# ESC3_1.net
KiCad netlist of a schematic drawn in Altium Designer
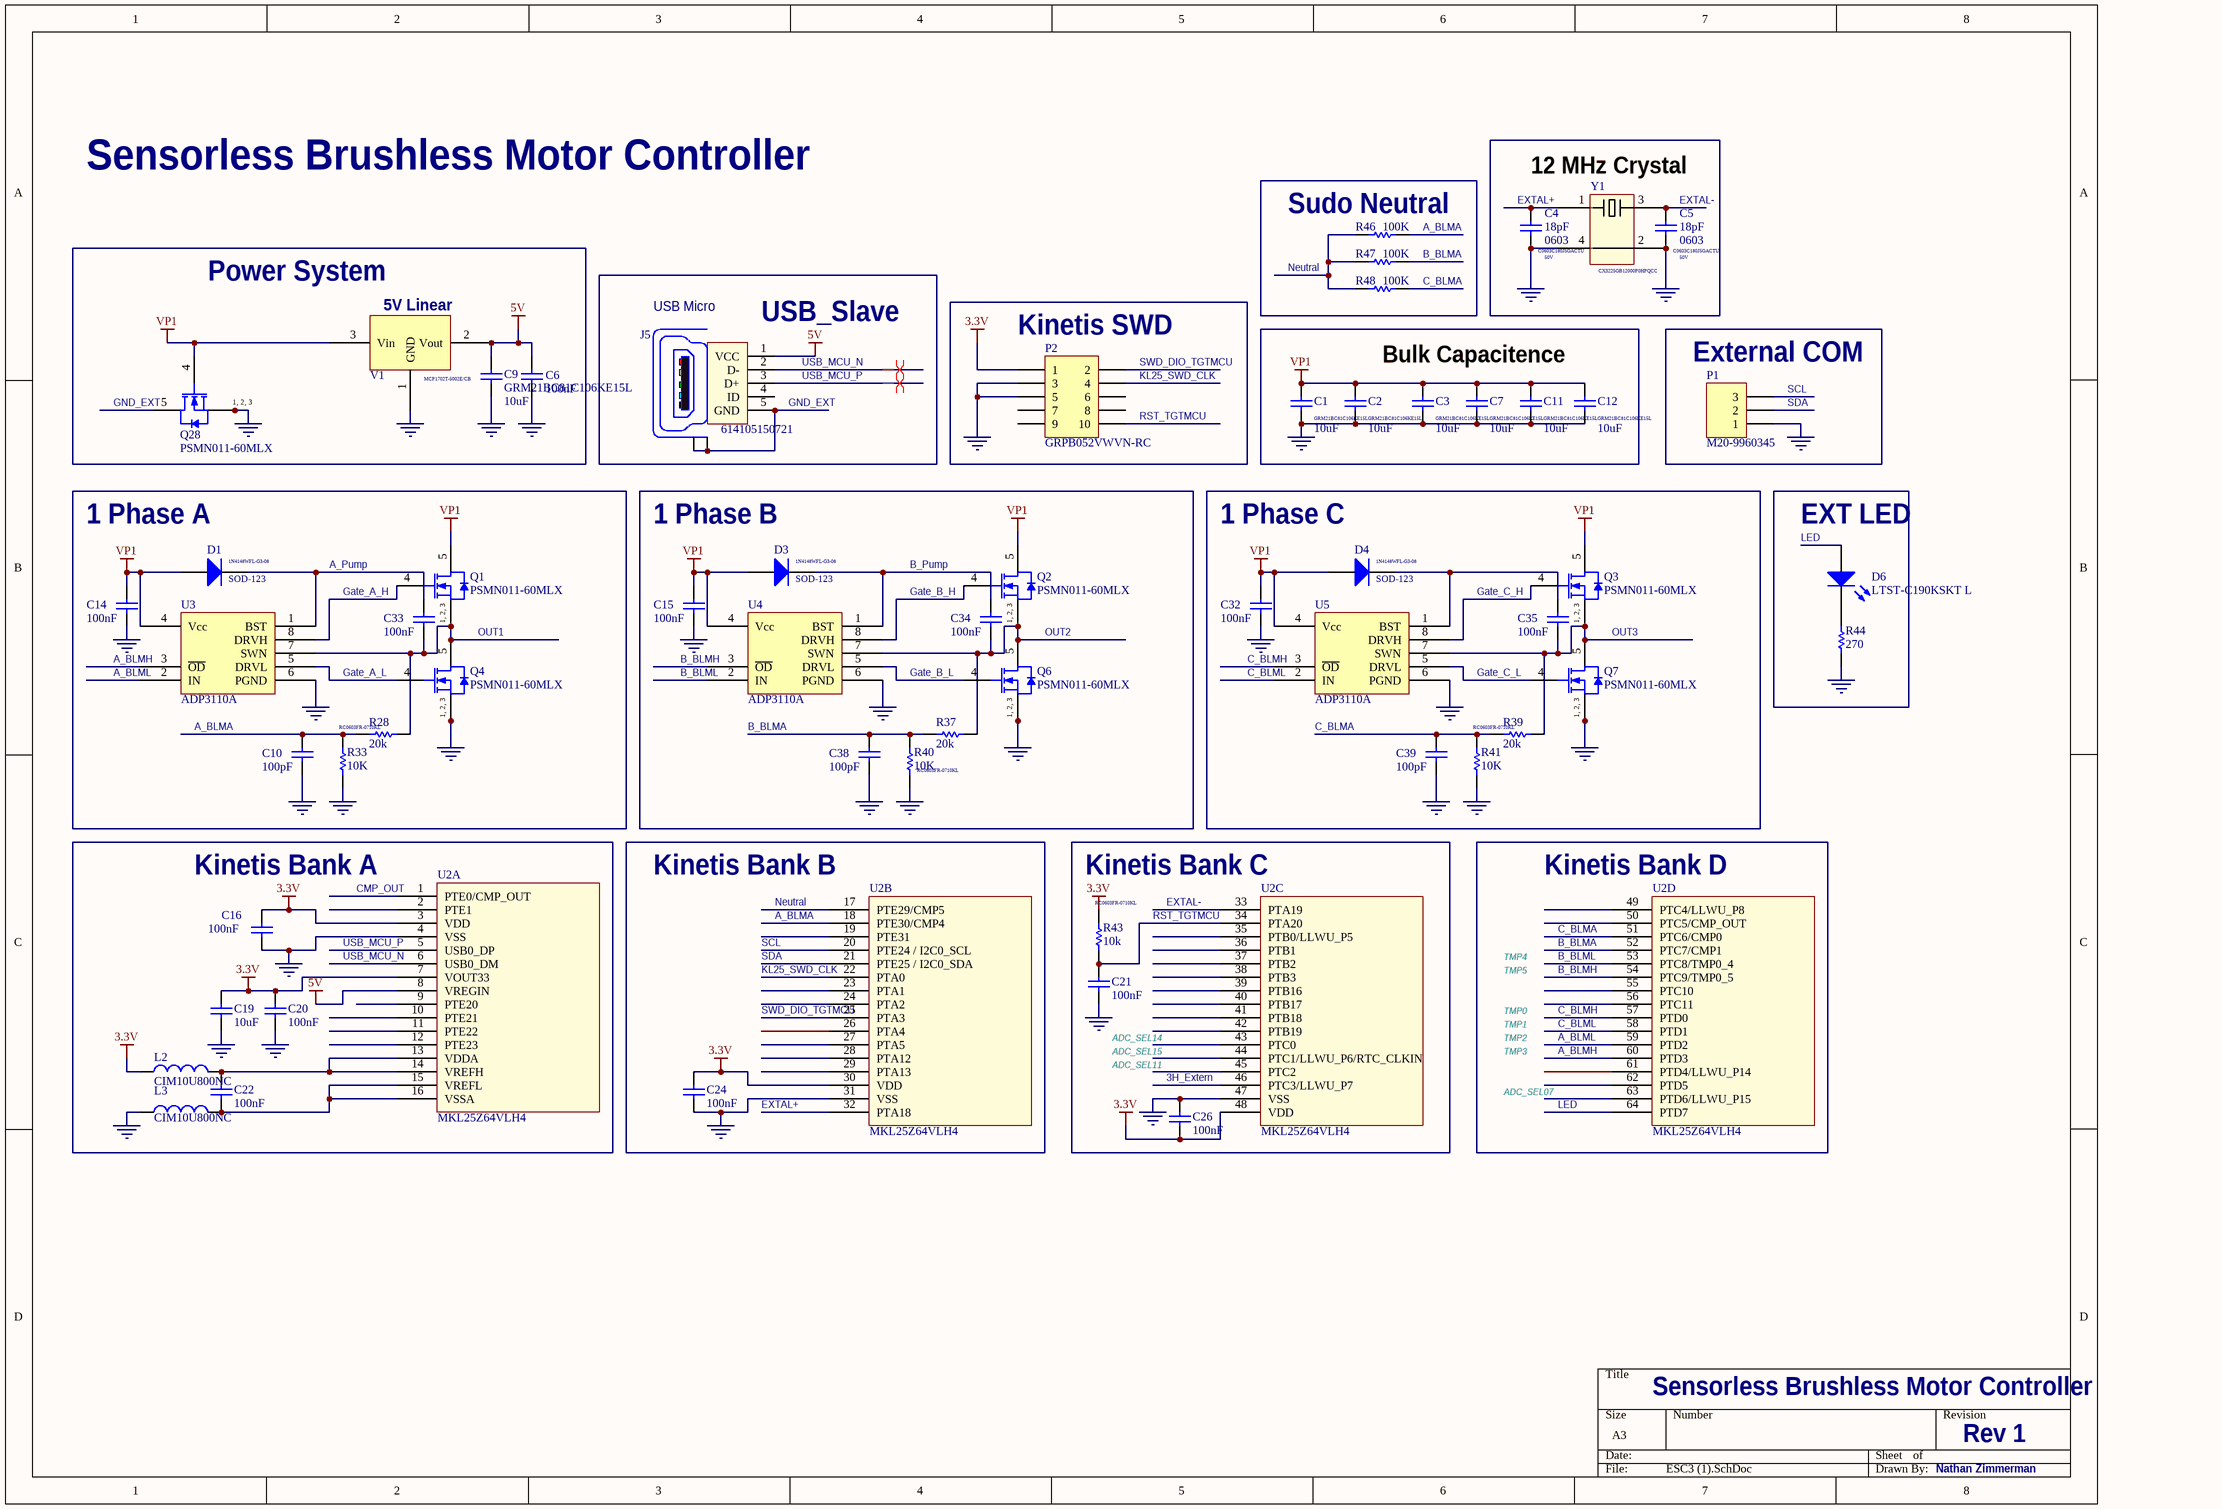
[diagram p0: ESC3 (1).SchDoc]

(export (version "E")
  (design (tool "Eeschema 10.0.6"))
  (components
    (comp (ref "C1")
      (value "GRM21BC81C106KE15L")
      (footprint "6-0805_MC")
      (fields (field (name "ALTIUM_VALUE") "10uF") (field (name "PUBLISHER") "Altium Limited"))
      (libsource (lib "Miscellaneous Devices") (part "Cap"))
    )
    (comp (ref "C2")
      (value "GRM21BC81C106KE15L")
      (footprint "6-0805_MC")
      (fields (field (name "ALTIUM_VALUE") "10uF") (field (name "PUBLISHER") "Altium Limited"))
      (libsource (lib "Miscellaneous Devices") (part "Cap"))
    )
    (comp (ref "C3")
      (value "GRM21BC81C106KE15L")
      (footprint "6-0805_MC")
      (fields (field (name "ALTIUM_VALUE") "10uF") (field (name "PUBLISHER") "Altium Limited"))
      (libsource (lib "Miscellaneous Devices") (part "Cap"))
    )
    (comp (ref "C4")
      (value "C0603C180J5GACTU")
      (footprint "1608[0603]C")
      (description "Capacitor (Semiconductor SIM Model)")
      (fields
        (field (name "PACKAGEREFERENCE") "0603")
        (field (name "ALTIUM_VALUE") "18pF")
        (field (name "VOLTAGE") "50V")
      )
      (libsource (lib "Miscellaneous Devices") (part "Cap Semi"))
    )
    (comp (ref "C5")
      (value "C0603C180J5GACTU")
      (footprint "1608[0603]C")
      (description "Capacitor (Semiconductor SIM Model)")
      (fields
        (field (name "PACKAGEREFERENCE") "0603")
        (field (name "ALTIUM_VALUE") "18pF")
        (field (name "VOLTAGE") "50V")
      )
      (libsource (lib "Miscellaneous Devices") (part "Cap Semi"))
    )
    (comp (ref "C6")
      (value "100nF")
      (footprint "1608[0603]C")
      (description "Capacitor (Semiconductor SIM Model)")
      (fields (field (name "Comment") "GRM188R71H104KA93D") (field (name "PUBLISHER") "Altium Limited"))
      (libsource (lib "Miscellaneous Devices") (part "Cap Semi"))
    )
    (comp (ref "C7")
      (value "GRM21BC81C106KE15L")
      (footprint "6-0805_MC")
      (fields (field (name "ALTIUM_VALUE") "10uF") (field (name "PUBLISHER") "Altium Limited"))
      (libsource (lib "Miscellaneous Devices") (part "Cap"))
    )
    (comp (ref "C9")
      (value "GRM21BC81C106KE15L")
      (footprint "6-0805_MC")
      (description "Capacitor")
      (fields (field (name "ALTIUM_VALUE") "10uF") (field (name "PUBLISHER") "Altium Limited"))
      (libsource (lib "Miscellaneous Devices") (part "Cap"))
    )
    (comp (ref "C10")
      (value "100pF")
      (footprint "1608[0603]C")
      (description "Capacitor (Semiconductor SIM Model)")
      (fields (field (name "Comment") "C1608C0G1H101J080AA") (field (name "PUBLISHER") "Altium Limited"))
      (libsource (lib "Miscellaneous Devices") (part "Cap Semi"))
    )
    (comp (ref "C11")
      (value "GRM21BC81C106KE15L")
      (footprint "6-0805_MC")
      (fields (field (name "ALTIUM_VALUE") "10uF") (field (name "PUBLISHER") "Altium Limited"))
      (libsource (lib "Miscellaneous Devices") (part "Cap"))
    )
    (comp (ref "C12")
      (value "GRM21BC81C106KE15L")
      (footprint "6-0805_MC")
      (fields (field (name "ALTIUM_VALUE") "10uF") (field (name "PUBLISHER") "Altium Limited"))
      (libsource (lib "Miscellaneous Devices") (part "Cap"))
    )
    (comp (ref "C14")
      (value "100nF")
      (footprint "1608[0603]C")
      (description "Capacitor (Semiconductor SIM Model)")
      (fields (field (name "Comment") "GRM188R71H104KA93D") (field (name "PUBLISHER") "Altium Limited"))
      (libsource (lib "Miscellaneous Devices") (part "Cap Semi"))
    )
    (comp (ref "C15")
      (value "100nF")
      (footprint "1608[0603]C")
      (description "Capacitor (Semiconductor SIM Model)")
      (fields (field (name "Comment") "GRM188R71H104KA93D") (field (name "PUBLISHER") "Altium Limited"))
      (libsource (lib "Miscellaneous Devices") (part "Cap Semi"))
    )
    (comp (ref "C16")
      (value "100nF")
      (footprint "1608[0603]C")
      (description "Capacitor (Semiconductor SIM Model)")
      (fields (field (name "Comment") "GRM188R71H104KA93D") (field (name "PUBLISHER") "Altium Limited"))
      (libsource (lib "Miscellaneous Devices") (part "Cap Semi"))
    )
    (comp (ref "C19")
      (value "10uF")
      (footprint "6-0805_MC")
      (description "Capacitor (Semiconductor SIM Model)")
      (fields (field (name "Comment") "GRM21BC81C106KE15L") (field (name "PUBLISHER") "Altium Limited"))
      (libsource (lib "Miscellaneous Devices") (part "Cap Semi"))
    )
    (comp (ref "C20")
      (value "100nF")
      (footprint "1608[0603]C")
      (description "Capacitor (Semiconductor SIM Model)")
      (fields (field (name "Comment") "GRM188R71H104KA93D") (field (name "PUBLISHER") "Altium Limited"))
      (libsource (lib "Miscellaneous Devices") (part "Cap Semi"))
    )
    (comp (ref "C21")
      (value "100nF")
      (footprint "1608[0603]C")
      (description "Capacitor (Semiconductor SIM Model)")
      (fields (field (name "Comment") "GRM188R71H104KA93D") (field (name "PUBLISHER") "Altium Limited"))
      (libsource (lib "Miscellaneous Devices") (part "Cap Semi"))
    )
    (comp (ref "C22")
      (value "100nF")
      (footprint "1608[0603]C")
      (description "Capacitor (Semiconductor SIM Model)")
      (fields (field (name "Comment") "GRM188R71H104KA93D") (field (name "PUBLISHER") "Altium Limited"))
      (libsource (lib "Miscellaneous Devices") (part "Cap Semi"))
    )
    (comp (ref "C24")
      (value "100nF")
      (footprint "1608[0603]C")
      (description "Capacitor (Semiconductor SIM Model)")
      (fields (field (name "Comment") "GRM188R71H104KA93D") (field (name "PUBLISHER") "Altium Limited"))
      (libsource (lib "Miscellaneous Devices") (part "Cap Semi"))
    )
    (comp (ref "C26")
      (value "100nF")
      (footprint "1608[0603]C")
      (description "Capacitor (Semiconductor SIM Model)")
      (fields (field (name "Comment") "GRM188R71H104KA93D") (field (name "PUBLISHER") "Altium Limited"))
      (libsource (lib "Miscellaneous Devices") (part "Cap Semi"))
    )
    (comp (ref "C32")
      (value "100nF")
      (footprint "1608[0603]C")
      (description "Capacitor (Semiconductor SIM Model)")
      (fields (field (name "Comment") "GRM188R71H104KA93D") (field (name "PUBLISHER") "Altium Limited"))
      (libsource (lib "Miscellaneous Devices") (part "Cap Semi"))
    )
    (comp (ref "C33")
      (value "100nF")
      (footprint "1608[0603]C")
      (description "Capacitor (Semiconductor SIM Model)")
      (fields (field (name "Comment") "GRM188R71H104KA93D") (field (name "PUBLISHER") "Altium Limited"))
      (libsource (lib "Miscellaneous Devices") (part "Cap Semi"))
    )
    (comp (ref "C34")
      (value "100nF")
      (footprint "1608[0603]C")
      (description "Capacitor (Semiconductor SIM Model)")
      (fields (field (name "Comment") "GRM188R71H104KA93D") (field (name "PUBLISHER") "Altium Limited"))
      (libsource (lib "Miscellaneous Devices") (part "Cap Semi"))
    )
    (comp (ref "C35")
      (value "100nF")
      (footprint "1608[0603]C")
      (description "Capacitor (Semiconductor SIM Model)")
      (fields (field (name "Comment") "GRM188R71H104KA93D") (field (name "PUBLISHER") "Altium Limited"))
      (libsource (lib "Miscellaneous Devices") (part "Cap Semi"))
    )
    (comp (ref "C38")
      (value "100pF")
      (footprint "1608[0603]C")
      (description "Capacitor (Semiconductor SIM Model)")
      (fields (field (name "Comment") "C1608C0G1H101J080AA") (field (name "PUBLISHER") "Altium Limited"))
      (libsource (lib "Miscellaneous Devices") (part "Cap Semi"))
    )
    (comp (ref "C39")
      (value "100pF")
      (footprint "1608[0603]C")
      (description "Capacitor (Semiconductor SIM Model)")
      (fields (field (name "Comment") "C1608C0G1H101J080AA") (field (name "PUBLISHER") "Altium Limited"))
      (libsource (lib "Miscellaneous Devices") (part "Cap Semi"))
    )
    (comp (ref "D1")
      (value "1N4148WFL-G3-08")
      (footprint "SOD123_3D")
      (description "High Conductance Fast Diode")
      (fields (field (name "PACKAGEREFERENCE") "SOD-123") (field (name "PUBLISHER") "Altium Limited"))
      (libsource (lib "Miscellaneous Devices") (part "Diode 1N4148"))
    )
    (comp (ref "D3")
      (value "1N4148WFL-G3-08")
      (footprint "SOD123_3D")
      (description "High Conductance Fast Diode")
      (fields (field (name "PACKAGEREFERENCE") "SOD-123") (field (name "PUBLISHER") "Altium Limited"))
      (libsource (lib "Miscellaneous Devices") (part "Diode 1N4148"))
    )
    (comp (ref "D4")
      (value "1N4148WFL-G3-08")
      (footprint "SOD123_3D")
      (description "High Conductance Fast Diode")
      (fields (field (name "PACKAGEREFERENCE") "SOD-123") (field (name "PUBLISHER") "Altium Limited"))
      (libsource (lib "Miscellaneous Devices") (part "Diode 1N4148"))
    )
    (comp (ref "D6")
      (value "LTST-C190KSKT L")
      (footprint "1608[0603]LED")
      (description "Typical BLUE SiC LED")
      (fields (field (name "PUBLISHER") "Altium Limited"))
      (libsource (lib "Miscellaneous Devices") (part "LED3"))
    )
    (comp (ref "J5")
      (value "614105150721")
      (footprint "USB_Micro_Vertical")
      (description "WR-COM_USB_Micro Type B_Vertical_THT")
      (fields
        (field (name "MANUFACTURER") "Würth Elektronik eiSos GmbH")
        (field (name "CREATED BY") "Karrer Zheng")
      )
      (libsource (lib "614105150721") (part "WR-Communication Connectors 614105150721"))
    )
    (comp (ref "L2")
      (value "CIM10U800NC")
      (footprint "1608[0603]L")
      (description "Inductor")
      (libsource (lib "Miscellaneous Devices") (part "Inductor"))
    )
    (comp (ref "L3")
      (value "CIM10U800NC")
      (footprint "1608[0603]L")
      (description "Inductor")
      (libsource (lib "Miscellaneous Devices") (part "Inductor"))
    )
    (comp (ref "P1")
      (value "M20-9960345")
      (footprint "HDR1X3")
      (description "Header, 3-Pin")
      (fields (field (name "PUBLISHER") "Altium Limited"))
      (libsource (lib "Miscellaneous Connectors") (part "Header 3"))
    )
    (comp (ref "P2")
      (value "GRPB052VWVN-RC")
      (footprint "MHDR2X5")
      (description "Header, 5-Pin, Dual row")
      (fields (field (name "PUBLISHER") "Altium Limited"))
      (libsource (lib "Miscellaneous Connectors") (part "Header 5X2"))
    )
    (comp (ref "Q1")
      (value "PSMN011-60MLX")
      (footprint "SOT1210_FET")
      (description "N-Channel Logic Level MOSFET, 60 V, 61 A, 5-Pin SOT1210, Reel")
      (fields (field (name "MANUFACTURER") "NXP Semiconductors"))
      (libsource (lib "altium-import") (part "root_0_CMP-1258-00026-1_"))
    )
    (comp (ref "Q2")
      (value "PSMN011-60MLX")
      (footprint "SOT1210_FET")
      (description "N-Channel Logic Level MOSFET, 60 V, 61 A, 5-Pin SOT1210, Reel")
      (fields (field (name "MANUFACTURER") "NXP Semiconductors"))
      (libsource (lib "altium-import") (part "root_0_CMP-1258-00026-1_"))
    )
    (comp (ref "Q3")
      (value "PSMN011-60MLX")
      (footprint "SOT1210_FET")
      (description "N-Channel Logic Level MOSFET, 60 V, 61 A, 5-Pin SOT1210, Reel")
      (fields (field (name "MANUFACTURER") "NXP Semiconductors"))
      (libsource (lib "altium-import") (part "root_0_CMP-1258-00026-1_"))
    )
    (comp (ref "Q4")
      (value "PSMN011-60MLX")
      (footprint "SOT1210_FET")
      (description "N-Channel Logic Level MOSFET, 60 V, 61 A, 5-Pin SOT1210, Reel")
      (fields (field (name "MANUFACTURER") "NXP Semiconductors"))
      (libsource (lib "altium-import") (part "root_0_CMP-1258-00026-1_"))
    )
    (comp (ref "Q6")
      (value "PSMN011-60MLX")
      (footprint "SOT1210_FET")
      (description "N-Channel Logic Level MOSFET, 60 V, 61 A, 5-Pin SOT1210, Reel")
      (fields (field (name "MANUFACTURER") "NXP Semiconductors"))
      (libsource (lib "altium-import") (part "root_0_CMP-1258-00026-1_"))
    )
    (comp (ref "Q7")
      (value "PSMN011-60MLX")
      (footprint "SOT1210_FET")
      (description "N-Channel Logic Level MOSFET, 60 V, 61 A, 5-Pin SOT1210, Reel")
      (fields (field (name "MANUFACTURER") "NXP Semiconductors"))
      (libsource (lib "altium-import") (part "root_0_CMP-1258-00026-1_"))
    )
    (comp (ref "Q28")
      (value "PSMN011-60MLX")
      (footprint "SOT1210_FET")
      (description "N-Channel Logic Level MOSFET, 60 V, 61 A, 5-Pin SOT1210, Reel")
      (fields (field (name "MANUFACTURER") "NXP Semiconductors"))
      (libsource (lib "altium-import") (part "root_3_mirrored_CMP-1258-00026-1_"))
    )
    (comp (ref "R28")
      (value "20k")
      (footprint "1608[0603]R")
      (description "Resistor")
      (fields (field (name "Comment") "Res1") (field (name "PUBLISHER") "Altium Limited"))
      (libsource (lib "Miscellaneous Devices") (part "Res1"))
    )
    (comp (ref "R33")
      (value "RC0603FR-0710KL")
      (footprint "1608[0603]R")
      (description "Resistor")
      (fields (field (name "ALTIUM_VALUE") "10K") (field (name "PUBLISHER") "Altium Limited"))
      (libsource (lib "Miscellaneous Devices") (part "Res1"))
    )
    (comp (ref "R37")
      (value "20k")
      (footprint "1608[0603]R")
      (description "Resistor")
      (fields (field (name "Comment") "Res1") (field (name "PUBLISHER") "Altium Limited"))
      (libsource (lib "Miscellaneous Devices") (part "Res1"))
    )
    (comp (ref "R39")
      (value "20k")
      (footprint "1608[0603]R")
      (description "Resistor")
      (fields (field (name "Comment") "Res1") (field (name "PUBLISHER") "Altium Limited"))
      (libsource (lib "Miscellaneous Devices") (part "Res1"))
    )
    (comp (ref "R40")
      (value "RC0603FR-0710KL")
      (footprint "1608[0603]R")
      (description "Resistor")
      (fields (field (name "ALTIUM_VALUE") "10K") (field (name "PUBLISHER") "Altium Limited"))
      (libsource (lib "Miscellaneous Devices") (part "Res1"))
    )
    (comp (ref "R41")
      (value "RC0603FR-0710KL")
      (footprint "1608[0603]R")
      (description "Resistor")
      (fields (field (name "ALTIUM_VALUE") "10K") (field (name "PUBLISHER") "Altium Limited"))
      (libsource (lib "Miscellaneous Devices") (part "Res1"))
    )
    (comp (ref "R43")
      (value "RC0603FR-0710KL")
      (footprint "1608[0603]R")
      (description "Resistor")
      (fields (field (name "ALTIUM_VALUE") "10k") (field (name "PUBLISHER") "Altium Limited"))
      (libsource (lib "Miscellaneous Devices") (part "Res1"))
    )
    (comp (ref "R44")
      (value "270")
      (footprint "1608[0603]R")
      (description "Resistor")
      (fields (field (name "Comment") "Res1") (field (name "PUBLISHER") "Altium Limited"))
      (libsource (lib "Miscellaneous Devices") (part "Res1"))
    )
    (comp (ref "R46")
      (value "100K")
      (footprint "1608[0603]R")
      (description "Resistor")
      (fields (field (name "Comment") "Res1") (field (name "PUBLISHER") "Altium Limited"))
      (libsource (lib "Miscellaneous Devices") (part "Res1"))
    )
    (comp (ref "R47")
      (value "100K")
      (footprint "1608[0603]R")
      (description "Resistor")
      (fields (field (name "Comment") "Res1") (field (name "PUBLISHER") "Altium Limited"))
      (libsource (lib "Miscellaneous Devices") (part "Res1"))
    )
    (comp (ref "R48")
      (value "100K")
      (footprint "1608[0603]R")
      (description "Resistor")
      (fields (field (name "Comment") "Res1") (field (name "PUBLISHER") "Altium Limited"))
      (libsource (lib "Miscellaneous Devices") (part "Res1"))
    )
    (comp (ref "U2")
      (value "MKL25Z64VLH4")
      (footprint "LQFP64_10mm_0.5mm")
      (description "MKL25Z64VLH4 MCU")
      (libsource (lib "MKL25Z64VLH4") (part "MKL25Z64VLH4"))
    )
    (comp (ref "U3")
      (value "ADP3110A")
      (footprint "SOIC8_3.9mm_body")
      (libsource (lib "ADP3110A") (part "ADP3110A"))
    )
    (comp (ref "U4")
      (value "ADP3110A")
      (footprint "SOIC8_3.9mm_body")
      (libsource (lib "ADP3110A") (part "ADP3110A"))
    )
    (comp (ref "U5")
      (value "ADP3110A")
      (footprint "SOIC8_3.9mm_body")
      (libsource (lib "ADP3110A") (part "ADP3110A"))
    )
    (comp (ref "V1")
      (value "MCP1702T-5002E/CB")
      (footprint "SOT-23B_M")
      (description "MCP1700 3.3V REG")
      (libsource (lib "MCP1700") (part "MCP1700"))
    )
    (comp (ref "Y1")
      (value "CX3225GB12000P0HPQCC")
      (footprint "3225_Crystal")
      (description "12MHz Micro Crystal")
      (libsource (lib "12MHz_micro_crystal") (part "12MHz_Crystal"))
    )
  )
  (nets
    (net (code "1") (name "/3H_Extern") (class "Default")
      (node (ref "U2") (pin "46") (pinfunction "PTC3/LLWU_P7_46") (pintype "passive"))
    )
    (net (code "2") (name "/A_BLMA") (class "Default")
      (node (ref "C10") (pin "2") (pinfunction "2_2") (pintype "passive"))
      (node (ref "R28") (pin "2") (pinfunction "2_2") (pintype "passive"))
      (node (ref "R33") (pin "1") (pinfunction "1_1") (pintype "passive"))
      (node (ref "R46") (pin "2") (pinfunction "2_2") (pintype "passive"))
      (node (ref "U2") (pin "18") (pinfunction "PTE30/CMP4_18") (pintype "passive"))
    )
    (net (code "3") (name "/A_BLMH") (class "Default")
      (node (ref "U2") (pin "60") (pinfunction "PTD3_60") (pintype "passive"))
      (node (ref "U3") (pin "3") (pinfunction "~{OD}_3") (pintype "passive"))
    )
    (net (code "4") (name "/A_BLML") (class "Default")
      (node (ref "U2") (pin "59") (pinfunction "PTD2_59") (pintype "passive"))
      (node (ref "U3") (pin "2") (pinfunction "IN_2") (pintype "passive"))
    )
    (net (code "5") (name "/A_Pump") (class "Default")
      (node (ref "C33") (pin "2") (pinfunction "2_2") (pintype "passive"))
      (node (ref "D1") (pin "2") (pinfunction "K_2") (pintype "passive"))
      (node (ref "U3") (pin "1") (pinfunction "BST_1") (pintype "passive"))
    )
    (net (code "6") (name "/B_BLMA") (class "Default")
      (node (ref "C38") (pin "2") (pinfunction "2_2") (pintype "passive"))
      (node (ref "R37") (pin "2") (pinfunction "2_2") (pintype "passive"))
      (node (ref "R40") (pin "1") (pinfunction "1_1") (pintype "passive"))
      (node (ref "R47") (pin "2") (pinfunction "2_2") (pintype "passive"))
      (node (ref "U2") (pin "52") (pinfunction "PTC7_52") (pintype "passive"))
    )
    (net (code "7") (name "/B_BLMH") (class "Default")
      (node (ref "U2") (pin "54") (pinfunction "PTC9_54") (pintype "passive"))
      (node (ref "U4") (pin "3") (pinfunction "~{OD}_3") (pintype "passive"))
    )
    (net (code "8") (name "/B_BLML") (class "Default")
      (node (ref "U2") (pin "53") (pinfunction "PTC8_53") (pintype "passive"))
      (node (ref "U4") (pin "2") (pinfunction "IN_2") (pintype "passive"))
    )
    (net (code "9") (name "/B_Pump") (class "Default")
      (node (ref "C34") (pin "2") (pinfunction "2_2") (pintype "passive"))
      (node (ref "D3") (pin "2") (pinfunction "K_2") (pintype "passive"))
      (node (ref "U4") (pin "1") (pinfunction "BST_1") (pintype "passive"))
    )
    (net (code "10") (name "/CMP_OUT") (class "Default")
      (node (ref "U2") (pin "1") (pinfunction "PTE0_1") (pintype "passive"))
    )
    (net (code "11") (name "/C_BLMA") (class "Default")
      (node (ref "C39") (pin "2") (pinfunction "2_2") (pintype "passive"))
      (node (ref "R39") (pin "2") (pinfunction "2_2") (pintype "passive"))
      (node (ref "R41") (pin "1") (pinfunction "1_1") (pintype "passive"))
      (node (ref "R48") (pin "2") (pinfunction "2_2") (pintype "passive"))
      (node (ref "U2") (pin "51") (pinfunction "PTC6/LLWU_P10_51") (pintype "passive"))
    )
    (net (code "12") (name "/C_BLMH") (class "Default")
      (node (ref "U2") (pin "57") (pinfunction "PTD0_57") (pintype "passive"))
      (node (ref "U5") (pin "3") (pinfunction "~{OD}_3") (pintype "passive"))
    )
    (net (code "13") (name "/C_BLML") (class "Default")
      (node (ref "U2") (pin "58") (pinfunction "PTD1_58") (pintype "passive"))
      (node (ref "U5") (pin "2") (pinfunction "IN_2") (pintype "passive"))
    )
    (net (code "14") (name "/EXTAL+") (class "Default")
      (node (ref "C4") (pin "2") (pinfunction "2_2") (pintype "passive"))
      (node (ref "U2") (pin "32") (pinfunction "PTA18_32") (pintype "passive"))
      (node (ref "Y1") (pin "1") (pinfunction "X1_1") (pintype "passive"))
    )
    (net (code "15") (name "/EXTAL-") (class "Default")
      (node (ref "C5") (pin "2") (pinfunction "2_2") (pintype "passive"))
      (node (ref "U2") (pin "33") (pinfunction "PTA19_33") (pintype "passive"))
      (node (ref "Y1") (pin "3") (pinfunction "X2_3") (pintype "passive"))
    )
    (net (code "16") (name "/GND_EXT") (class "Default")
      (node (ref "J5") (pin "5") (pinfunction "GND_5") (pintype "passive"))
      (node (ref "J5") (pin "Z1") (pinfunction "Shield_Z1") (pintype "passive"))
      (node (ref "J5") (pin "Z2") (pinfunction "Shield_Z2") (pintype "passive"))
      (node (ref "Q28") (pin "5") (pinfunction "D_5") (pintype "passive"))
    )
    (net (code "17") (name "/Gate_A_H") (class "Default")
      (node (ref "Q1") (pin "4") (pinfunction "G_4") (pintype "passive"))
      (node (ref "U3") (pin "8") (pinfunction "DRVH_8") (pintype "passive"))
    )
    (net (code "18") (name "/Gate_A_L") (class "Default")
      (node (ref "Q4") (pin "4") (pinfunction "G_4") (pintype "passive"))
      (node (ref "U3") (pin "5") (pinfunction "DRVL_5") (pintype "passive"))
    )
    (net (code "19") (name "/Gate_B_H") (class "Default")
      (node (ref "Q2") (pin "4") (pinfunction "G_4") (pintype "passive"))
      (node (ref "U4") (pin "8") (pinfunction "DRVH_8") (pintype "passive"))
    )
    (net (code "20") (name "/Gate_B_L") (class "Default")
      (node (ref "Q6") (pin "4") (pinfunction "G_4") (pintype "passive"))
      (node (ref "U4") (pin "5") (pinfunction "DRVL_5") (pintype "passive"))
    )
    (net (code "21") (name "/Gate_C_H") (class "Default")
      (node (ref "Q3") (pin "4") (pinfunction "G_4") (pintype "passive"))
      (node (ref "U5") (pin "8") (pinfunction "DRVH_8") (pintype "passive"))
    )
    (net (code "22") (name "/Gate_C_L") (class "Default")
      (node (ref "Q7") (pin "4") (pinfunction "G_4") (pintype "passive"))
      (node (ref "U5") (pin "5") (pinfunction "DRVL_5") (pintype "passive"))
    )
    (net (code "23") (name "/KL25_SWD_CLK") (class "Default")
      (node (ref "P2") (pin "4") (pinfunction "4_4") (pintype "passive"))
      (node (ref "U2") (pin "22") (pinfunction "PTA0_22") (pintype "passive"))
    )
    (net (code "24") (name "/LED") (class "Default")
      (node (ref "D6") (pin "1") (pinfunction "A_1") (pintype "passive"))
      (node (ref "U2") (pin "64") (pinfunction "PTD7_64") (pintype "passive"))
    )
    (net (code "25") (name "/Neutral") (class "Default")
      (node (ref "R46") (pin "1") (pinfunction "1_1") (pintype "passive"))
      (node (ref "R47") (pin "1") (pinfunction "1_1") (pintype "passive"))
      (node (ref "R48") (pin "1") (pinfunction "1_1") (pintype "passive"))
      (node (ref "U2") (pin "17") (pinfunction "PTE29/CMP5_17") (pintype "passive"))
    )
    (net (code "26") (name "/OUT1") (class "Default")
      (node (ref "C33") (pin "1") (pinfunction "1_1") (pintype "passive"))
      (node (ref "Q1") (pin "1") (pinfunction "S_1") (pintype "passive"))
      (node (ref "Q1") (pin "2") (pinfunction "S_2") (pintype "passive"))
      (node (ref "Q1") (pin "3") (pinfunction "S_3") (pintype "passive"))
      (node (ref "Q4") (pin "5") (pinfunction "D_5") (pintype "passive"))
      (node (ref "R28") (pin "1") (pinfunction "1_1") (pintype "passive"))
      (node (ref "U3") (pin "7") (pinfunction "SWN_7") (pintype "passive"))
    )
    (net (code "27") (name "/OUT2") (class "Default")
      (node (ref "C34") (pin "1") (pinfunction "1_1") (pintype "passive"))
      (node (ref "Q2") (pin "1") (pinfunction "S_1") (pintype "passive"))
      (node (ref "Q2") (pin "2") (pinfunction "S_2") (pintype "passive"))
      (node (ref "Q2") (pin "3") (pinfunction "S_3") (pintype "passive"))
      (node (ref "Q6") (pin "5") (pinfunction "D_5") (pintype "passive"))
      (node (ref "R37") (pin "1") (pinfunction "1_1") (pintype "passive"))
      (node (ref "U4") (pin "7") (pinfunction "SWN_7") (pintype "passive"))
    )
    (net (code "28") (name "/OUT3") (class "Default")
      (node (ref "C35") (pin "1") (pinfunction "1_1") (pintype "passive"))
      (node (ref "Q3") (pin "1") (pinfunction "S_1") (pintype "passive"))
      (node (ref "Q3") (pin "2") (pinfunction "S_2") (pintype "passive"))
      (node (ref "Q3") (pin "3") (pinfunction "S_3") (pintype "passive"))
      (node (ref "Q7") (pin "5") (pinfunction "D_5") (pintype "passive"))
      (node (ref "R39") (pin "1") (pinfunction "1_1") (pintype "passive"))
      (node (ref "U5") (pin "7") (pinfunction "SWN_7") (pintype "passive"))
    )
    (net (code "29") (name "/RST_TGTMCU") (class "Default")
      (node (ref "C21") (pin "2") (pinfunction "2_2") (pintype "passive"))
      (node (ref "P2") (pin "10") (pinfunction "10_10") (pintype "passive"))
      (node (ref "R43") (pin "1") (pinfunction "1_1") (pintype "passive"))
      (node (ref "U2") (pin "34") (pinfunction "PTA20_34") (pintype "passive"))
    )
    (net (code "30") (name "/SCL") (class "Default")
      (node (ref "P1") (pin "3") (pinfunction "3_3") (pintype "passive"))
      (node (ref "U2") (pin "20") (pinfunction "PTE24_/_I2C0_SCL_20") (pintype "passive"))
    )
    (net (code "31") (name "/SDA") (class "Default")
      (node (ref "P1") (pin "2") (pinfunction "2_2") (pintype "passive"))
      (node (ref "U2") (pin "21") (pinfunction "PTE25_/_I2C0_SDA_21") (pintype "passive"))
    )
    (net (code "32") (name "/SWD_DIO_TGTMCU") (class "Default")
      (node (ref "P2") (pin "2") (pinfunction "2_2") (pintype "passive"))
      (node (ref "U2") (pin "25") (pinfunction "PTA3_25") (pintype "passive"))
    )
    (net (code "33") (name "/USB_MCU_N") (class "Default")
      (node (ref "J5") (pin "2") (pinfunction "D-_2") (pintype "passive"))
      (node (ref "U2") (pin "6") (pinfunction "USB0_DM_6") (pintype "passive"))
    )
    (net (code "34") (name "/USB_MCU_P") (class "Default")
      (node (ref "J5") (pin "3") (pinfunction "D+_3") (pintype "passive"))
      (node (ref "U2") (pin "5") (pinfunction "USB0_DP_5") (pintype "passive"))
    )
    (net (code "35") (name "3.3V") (class "Default")
      (node (ref "C16") (pin "2") (pinfunction "2_2") (pintype "passive"))
      (node (ref "C19") (pin "1") (pinfunction "1_1") (pintype "passive"))
      (node (ref "C20") (pin "1") (pinfunction "1_1") (pintype "passive"))
      (node (ref "C24") (pin "2") (pinfunction "2_2") (pintype "passive"))
      (node (ref "C26") (pin "1") (pinfunction "1_1") (pintype "passive"))
      (node (ref "L2") (pin "2") (pinfunction "2_2") (pintype "passive"))
      (node (ref "P2") (pin "1") (pinfunction "1_1") (pintype "passive"))
      (node (ref "R43") (pin "2") (pinfunction "2_2") (pintype "passive"))
      (node (ref "U2") (pin "3") (pinfunction "VDD_3") (pintype "passive"))
      (node (ref "U2") (pin "30") (pinfunction "VDD_30") (pintype "passive"))
      (node (ref "U2") (pin "48") (pinfunction "VDD_48") (pintype "passive"))
      (node (ref "U2") (pin "7") (pinfunction "VOUT33_7") (pintype "passive"))
    )
    (net (code "36") (name "5V") (class "Default")
      (node (ref "C6") (pin "2") (pinfunction "2_2") (pintype "passive"))
      (node (ref "C9") (pin "2") (pinfunction "2_2") (pintype "passive"))
      (node (ref "J5") (pin "1") (pinfunction "VCC_1") (pintype "passive"))
      (node (ref "U2") (pin "8") (pinfunction "VREGIN_8") (pintype "passive"))
      (node (ref "V1") (pin "2") (pinfunction "Vout_2") (pintype "passive"))
    )
    (net (code "37") (name "GND") (class "Default")
      (node (ref "C1") (pin "1") (pinfunction "1_1") (pintype "passive"))
      (node (ref "C10") (pin "1") (pinfunction "1_1") (pintype "passive"))
      (node (ref "C11") (pin "1") (pinfunction "1_1") (pintype "passive"))
      (node (ref "C12") (pin "1") (pinfunction "1_1") (pintype "passive"))
      (node (ref "C14") (pin "1") (pinfunction "1_1") (pintype "passive"))
      (node (ref "C15") (pin "1") (pinfunction "1_1") (pintype "passive"))
      (node (ref "C16") (pin "1") (pinfunction "1_1") (pintype "passive"))
      (node (ref "C19") (pin "2") (pinfunction "2_2") (pintype "passive"))
      (node (ref "C2") (pin "1") (pinfunction "1_1") (pintype "passive"))
      (node (ref "C20") (pin "2") (pinfunction "2_2") (pintype "passive"))
      (node (ref "C21") (pin "1") (pinfunction "1_1") (pintype "passive"))
      (node (ref "C24") (pin "1") (pinfunction "1_1") (pintype "passive"))
      (node (ref "C26") (pin "2") (pinfunction "2_2") (pintype "passive"))
      (node (ref "C3") (pin "1") (pinfunction "1_1") (pintype "passive"))
      (node (ref "C32") (pin "1") (pinfunction "1_1") (pintype "passive"))
      (node (ref "C38") (pin "1") (pinfunction "1_1") (pintype "passive"))
      (node (ref "C39") (pin "1") (pinfunction "1_1") (pintype "passive"))
      (node (ref "C4") (pin "1") (pinfunction "1_1") (pintype "passive"))
      (node (ref "C5") (pin "1") (pinfunction "1_1") (pintype "passive"))
      (node (ref "C6") (pin "1") (pinfunction "1_1") (pintype "passive"))
      (node (ref "C7") (pin "1") (pinfunction "1_1") (pintype "passive"))
      (node (ref "C9") (pin "1") (pinfunction "1_1") (pintype "passive"))
      (node (ref "L3") (pin "2") (pinfunction "2_2") (pintype "passive"))
      (node (ref "P1") (pin "1") (pinfunction "1_1") (pintype "passive"))
      (node (ref "P2") (pin "3") (pinfunction "3_3") (pintype "passive"))
      (node (ref "P2") (pin "5") (pinfunction "5_5") (pintype "passive"))
      (node (ref "Q28") (pin "1") (pinfunction "S_1") (pintype "passive"))
      (node (ref "Q28") (pin "2") (pinfunction "S_2") (pintype "passive"))
      (node (ref "Q28") (pin "3") (pinfunction "S_3") (pintype "passive"))
      (node (ref "Q4") (pin "1") (pinfunction "S_1") (pintype "passive"))
      (node (ref "Q4") (pin "2") (pinfunction "S_2") (pintype "passive"))
      (node (ref "Q4") (pin "3") (pinfunction "S_3") (pintype "passive"))
      (node (ref "Q6") (pin "1") (pinfunction "S_1") (pintype "passive"))
      (node (ref "Q6") (pin "2") (pinfunction "S_2") (pintype "passive"))
      (node (ref "Q6") (pin "3") (pinfunction "S_3") (pintype "passive"))
      (node (ref "Q7") (pin "1") (pinfunction "S_1") (pintype "passive"))
      (node (ref "Q7") (pin "2") (pinfunction "S_2") (pintype "passive"))
      (node (ref "Q7") (pin "3") (pinfunction "S_3") (pintype "passive"))
      (node (ref "R33") (pin "2") (pinfunction "2_2") (pintype "passive"))
      (node (ref "R40") (pin "2") (pinfunction "2_2") (pintype "passive"))
      (node (ref "R41") (pin "2") (pinfunction "2_2") (pintype "passive"))
      (node (ref "R44") (pin "2") (pinfunction "2_2") (pintype "passive"))
      (node (ref "U2") (pin "31") (pinfunction "VSS_31") (pintype "passive"))
      (node (ref "U2") (pin "4") (pinfunction "VSS_4") (pintype "passive"))
      (node (ref "U2") (pin "47") (pinfunction "VSS_47") (pintype "passive"))
      (node (ref "U3") (pin "6") (pinfunction "PGND_6") (pintype "passive"))
      (node (ref "U4") (pin "6") (pinfunction "PGND_6") (pintype "passive"))
      (node (ref "U5") (pin "6") (pinfunction "PGND_6") (pintype "passive"))
      (node (ref "V1") (pin "1") (pinfunction "GND_1") (pintype "passive"))
      (node (ref "Y1") (pin "2") (pinfunction "GND_2") (pintype "passive"))
      (node (ref "Y1") (pin "4") (pinfunction "GND_4") (pintype "passive"))
    )
    (net (code "38") (name "Net-(D4-K)") (class "Default")
      (node (ref "C35") (pin "2") (pinfunction "2_2") (pintype "passive"))
      (node (ref "D4") (pin "2") (pinfunction "K_2") (pintype "passive"))
      (node (ref "U5") (pin "1") (pinfunction "BST_1") (pintype "passive"))
    )
    (net (code "39") (name "Net-(D6-K)") (class "Default")
      (node (ref "D6") (pin "2") (pinfunction "K_2") (pintype "passive"))
      (node (ref "R44") (pin "1") (pinfunction "1_1") (pintype "passive"))
    )
    (net (code "40") (name "Net-(U2A-VDDA)") (class "Default")
      (node (ref "C22") (pin "2") (pinfunction "2_2") (pintype "passive"))
      (node (ref "L2") (pin "1") (pinfunction "1_1") (pintype "passive"))
      (node (ref "U2") (pin "13") (pinfunction "VDDA_13") (pintype "passive"))
      (node (ref "U2") (pin "14") (pinfunction "VREFH_14") (pintype "passive"))
    )
    (net (code "41") (name "Net-(U2A-VREFL)") (class "Default")
      (node (ref "C22") (pin "1") (pinfunction "1_1") (pintype "passive"))
      (node (ref "L3") (pin "1") (pinfunction "1_1") (pintype "passive"))
      (node (ref "U2") (pin "15") (pinfunction "VREFL_15") (pintype "passive"))
      (node (ref "U2") (pin "16") (pinfunction "VSSA_16") (pintype "passive"))
    )
    (net (code "42") (name "VP1") (class "Default")
      (node (ref "C1") (pin "2") (pinfunction "2_2") (pintype "passive"))
      (node (ref "C11") (pin "2") (pinfunction "2_2") (pintype "passive"))
      (node (ref "C12") (pin "2") (pinfunction "2_2") (pintype "passive"))
      (node (ref "C14") (pin "2") (pinfunction "2_2") (pintype "passive"))
      (node (ref "C15") (pin "2") (pinfunction "2_2") (pintype "passive"))
      (node (ref "C2") (pin "2") (pinfunction "2_2") (pintype "passive"))
      (node (ref "C3") (pin "2") (pinfunction "2_2") (pintype "passive"))
      (node (ref "C32") (pin "2") (pinfunction "2_2") (pintype "passive"))
      (node (ref "C7") (pin "2") (pinfunction "2_2") (pintype "passive"))
      (node (ref "D1") (pin "1") (pinfunction "A_1") (pintype "passive"))
      (node (ref "D3") (pin "1") (pinfunction "A_1") (pintype "passive"))
      (node (ref "D4") (pin "1") (pinfunction "A_1") (pintype "passive"))
      (node (ref "Q1") (pin "5") (pinfunction "D_5") (pintype "passive"))
      (node (ref "Q2") (pin "5") (pinfunction "D_5") (pintype "passive"))
      (node (ref "Q28") (pin "4") (pinfunction "G_4") (pintype "passive"))
      (node (ref "Q3") (pin "5") (pinfunction "D_5") (pintype "passive"))
      (node (ref "U3") (pin "4") (pinfunction "Vcc_4") (pintype "passive"))
      (node (ref "U4") (pin "4") (pinfunction "Vcc_4") (pintype "passive"))
      (node (ref "U5") (pin "4") (pinfunction "Vcc_4") (pintype "passive"))
      (node (ref "V1") (pin "3") (pinfunction "Vin_3") (pintype "passive"))
    )
    (net (code "43") (name "unconnected-(J5-ID-Pad4)") (class "Default")
      (node (ref "J5") (pin "4") (pinfunction "ID_4") (pintype "passive"))
    )
    (net (code "44") (name "unconnected-(P2-Pad6)") (class "Default")
      (node (ref "P2") (pin "6") (pinfunction "6_6") (pintype "passive"))
    )
    (net (code "45") (name "unconnected-(P2-Pad7)") (class "Default")
      (node (ref "P2") (pin "7") (pinfunction "7_7") (pintype "passive"))
    )
    (net (code "46") (name "unconnected-(P2-Pad8)") (class "Default")
      (node (ref "P2") (pin "8") (pinfunction "8_8") (pintype "passive"))
    )
    (net (code "47") (name "unconnected-(P2-Pad9)") (class "Default")
      (node (ref "P2") (pin "9") (pinfunction "9_9") (pintype "passive"))
    )
    (net (code "48") (name "unconnected-(U2A-PTE1-Pad2)") (class "Default")
      (node (ref "U2") (pin "2") (pinfunction "PTE1_2") (pintype "passive"))
    )
    (net (code "49") (name "unconnected-(U2A-PTE20-Pad9)") (class "Default")
      (node (ref "U2") (pin "9") (pinfunction "PTE20_9") (pintype "passive"))
    )
    (net (code "50") (name "unconnected-(U2A-PTE21-Pad10)") (class "Default")
      (node (ref "U2") (pin "10") (pinfunction "PTE21_10") (pintype "passive"))
    )
    (net (code "51") (name "unconnected-(U2A-PTE22-Pad11)") (class "Default")
      (node (ref "U2") (pin "11") (pinfunction "PTE22_11") (pintype "passive"))
    )
    (net (code "52") (name "unconnected-(U2A-PTE23-Pad12)") (class "Default")
      (node (ref "U2") (pin "12") (pinfunction "PTE23_12") (pintype "passive"))
    )
    (net (code "53") (name "unconnected-(U2B-PTA1-Pad23)") (class "Default")
      (node (ref "U2") (pin "23") (pinfunction "PTA1_23") (pintype "passive"))
    )
    (net (code "54") (name "unconnected-(U2B-PTA2-Pad24)") (class "Default")
      (node (ref "U2") (pin "24") (pinfunction "PTA2_24") (pintype "passive"))
    )
    (net (code "55") (name "unconnected-(U2B-PTA4-Pad26)") (class "Default")
      (node (ref "U2") (pin "26") (pinfunction "PTA4_26") (pintype "passive"))
    )
    (net (code "56") (name "unconnected-(U2B-PTA5-Pad27)") (class "Default")
      (node (ref "U2") (pin "27") (pinfunction "PTA5_27") (pintype "passive"))
    )
    (net (code "57") (name "unconnected-(U2B-PTA12-Pad28)") (class "Default")
      (node (ref "U2") (pin "28") (pinfunction "PTA12_28") (pintype "passive"))
    )
    (net (code "58") (name "unconnected-(U2B-PTA13-Pad29)") (class "Default")
      (node (ref "U2") (pin "29") (pinfunction "PTA13_29") (pintype "passive"))
    )
    (net (code "59") (name "unconnected-(U2B-PTE31-Pad19)") (class "Default")
      (node (ref "U2") (pin "19") (pinfunction "PTE31_19") (pintype "passive"))
    )
    (net (code "60") (name "unconnected-(U2C-PTB0{slash}LLWU_P5-Pad35)") (class "Default")
      (node (ref "U2") (pin "35") (pinfunction "PTB0/LLWU_P5_35") (pintype "passive"))
    )
    (net (code "61") (name "unconnected-(U2C-PTB1-Pad36)") (class "Default")
      (node (ref "U2") (pin "36") (pinfunction "PTB1_36") (pintype "passive"))
    )
    (net (code "62") (name "unconnected-(U2C-PTB2-Pad37)") (class "Default")
      (node (ref "U2") (pin "37") (pinfunction "PTB2_37") (pintype "passive"))
    )
    (net (code "63") (name "unconnected-(U2C-PTB3-Pad38)") (class "Default")
      (node (ref "U2") (pin "38") (pinfunction "PTB3_38") (pintype "passive"))
    )
    (net (code "64") (name "unconnected-(U2C-PTB16-Pad39)") (class "Default")
      (node (ref "U2") (pin "39") (pinfunction "PTB16_39") (pintype "passive"))
    )
    (net (code "65") (name "unconnected-(U2C-PTB17-Pad40)") (class "Default")
      (node (ref "U2") (pin "40") (pinfunction "PTB17_40") (pintype "passive"))
    )
    (net (code "66") (name "unconnected-(U2C-PTB18-Pad41)") (class "Default")
      (node (ref "U2") (pin "41") (pinfunction "PTB18_41") (pintype "passive"))
    )
    (net (code "67") (name "unconnected-(U2C-PTB19-Pad42)") (class "Default")
      (node (ref "U2") (pin "42") (pinfunction "PTB19_42") (pintype "passive"))
    )
    (net (code "68") (name "unconnected-(U2C-PTC0-Pad43)") (class "Default")
      (node (ref "U2") (pin "43") (pinfunction "PTC0_43") (pintype "passive"))
    )
    (net (code "69") (name "unconnected-(U2C-PTC1{slash}LLWU_P6{slash}RTC_CLKIN-Pad44)") (class "Default")
      (node (ref "U2") (pin "44") (pinfunction "PTC1/LLWU_P6/RTC_CLKIN_44") (pintype "passive"))
    )
    (net (code "70") (name "unconnected-(U2C-PTC2-Pad45)") (class "Default")
      (node (ref "U2") (pin "45") (pinfunction "PTC2_45") (pintype "passive"))
    )
    (net (code "71") (name "unconnected-(U2D-PTC4{slash}LLWU_P8-Pad49)") (class "Default")
      (node (ref "U2") (pin "49") (pinfunction "PTC4/LLWU_P8_49") (pintype "passive"))
    )
    (net (code "72") (name "unconnected-(U2D-PTC5{slash}LLWU_P9-Pad50)") (class "Default")
      (node (ref "U2") (pin "50") (pinfunction "PTC5/LLWU_P9_50") (pintype "passive"))
    )
    (net (code "73") (name "unconnected-(U2D-PTC10-Pad55)") (class "Default")
      (node (ref "U2") (pin "55") (pinfunction "PTC10_55") (pintype "passive"))
    )
    (net (code "74") (name "unconnected-(U2D-PTC11-Pad56)") (class "Default")
      (node (ref "U2") (pin "56") (pinfunction "PTC11_56") (pintype "passive"))
    )
    (net (code "75") (name "unconnected-(U2D-PTD4{slash}LLWU_P14-Pad61)") (class "Default")
      (node (ref "U2") (pin "61") (pinfunction "PTD4/LLWU_P14_61") (pintype "passive"))
    )
    (net (code "76") (name "unconnected-(U2D-PTD5-Pad62)") (class "Default")
      (node (ref "U2") (pin "62") (pinfunction "PTD5_62") (pintype "passive"))
    )
    (net (code "77") (name "unconnected-(U2D-PTD6{slash}LLWU_P15-Pad63)") (class "Default")
      (node (ref "U2") (pin "63") (pinfunction "PTD6/LLWU_P15_63") (pintype "passive"))
    )
  )
)
